# PFC_CurrentSensor_v3.net
KiCad netlist of a schematic drawn in Altium Designer
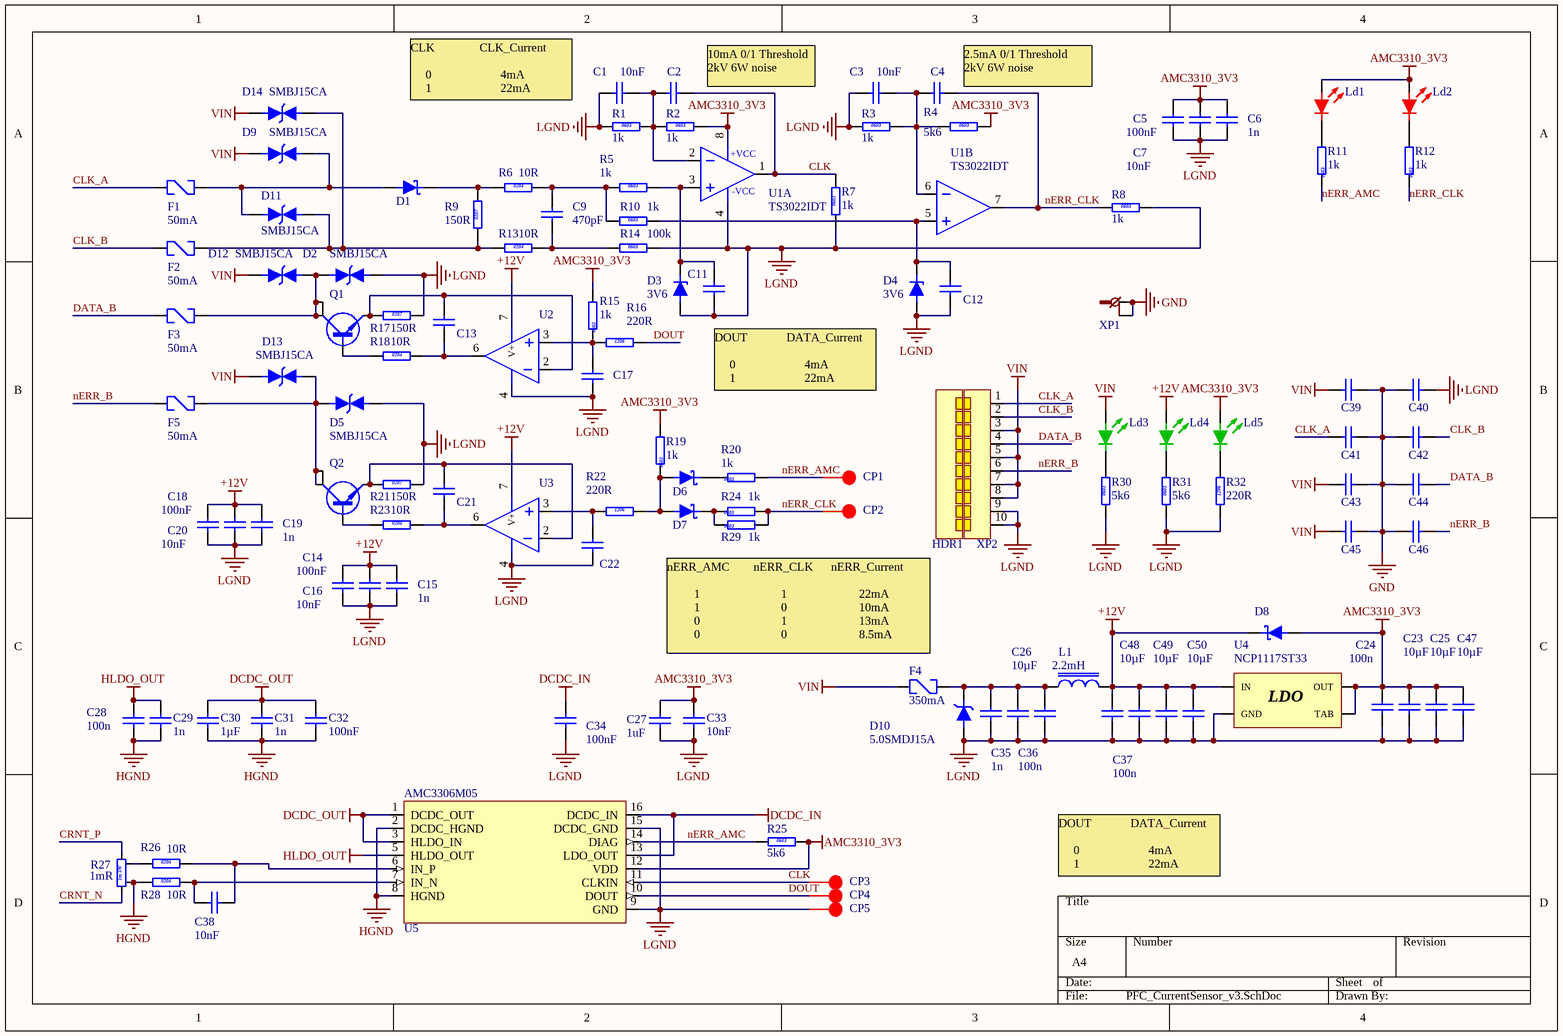
[diagram p0: PFC_CurrentSensor_v3.SchDoc]

(export (version "E")
  (design (tool "Eeschema 10.0.6"))
  (components
    (comp (ref "C1")
      (value "10nF")
      (footprint "CAP1206")
      (description "CAPACITOR UNPOLARIZED")
      (libsource (lib "components") (part "C103/50V/1206"))
    )
    (comp (ref "C2")
      (value "100p/100V/0603")
      (footprint "CAP0603")
      (description "CAPACITOR UNPOLARIZED")
      (libsource (lib "components") (part "C101/100V/0603"))
    )
    (comp (ref "C3")
      (value "10nF")
      (footprint "CAP1206")
      (description "CAPACITOR UNPOLARIZED")
      (libsource (lib "components") (part "C103/50V/1206"))
    )
    (comp (ref "C4")
      (value "100p/100V/0603")
      (footprint "CAP0603")
      (description "CAPACITOR UNPOLARIZED")
      (libsource (lib "components") (part "C101/100V/0603"))
    )
    (comp (ref "C5")
      (value "100nF")
      (footprint "CAP1206")
      (description "CAPACITOR UNPOLARIZED")
      (libsource (lib "components") (part "C104/50V/NP0/1206"))
    )
    (comp (ref "C6")
      (value "1n")
      (footprint "CAP0603")
      (description "CAPACITOR UNPOLARIZED")
      (libsource (lib "components") (part "C102/25V/0603"))
    )
    (comp (ref "C7")
      (value "10nF")
      (footprint "CAP1206")
      (description "CAPACITOR UNPOLARIZED")
      (libsource (lib "components") (part "C103/50V/1206"))
    )
    (comp (ref "C9")
      (value "470pF")
      (footprint "CAP1206")
      (description "CAPACITOR UNPOLARIZED")
      (libsource (lib "components") (part "C471/100V/1206/C0G"))
    )
    (comp (ref "C11")
      (value "100p/100V/0603")
      (footprint "CAP0603")
      (description "CAPACITOR UNPOLARIZED")
      (libsource (lib "components") (part "C101/100V/0603"))
    )
    (comp (ref "C12")
      (value "100p/100V/0603")
      (footprint "CAP0603")
      (description "CAPACITOR UNPOLARIZED")
      (libsource (lib "components") (part "C101/100V/0603"))
    )
    (comp (ref "C13")
      (value "100p/100V/0603")
      (footprint "CAP0603")
      (description "CAPACITOR UNPOLARIZED")
      (libsource (lib "components") (part "C101/100V/0603"))
    )
    (comp (ref "C14")
      (value "100nF")
      (footprint "CAP1206")
      (description "CAPACITOR UNPOLARIZED")
      (libsource (lib "components") (part "C104/50V/NP0/1206"))
    )
    (comp (ref "C15")
      (value "1n")
      (footprint "CAP0603")
      (description "CAPACITOR UNPOLARIZED")
      (libsource (lib "components") (part "C102/25V/0603"))
    )
    (comp (ref "C16")
      (value "10nF")
      (footprint "CAP1206")
      (description "CAPACITOR UNPOLARIZED")
      (libsource (lib "components") (part "C103/50V/1206"))
    )
    (comp (ref "C17")
      (value "100p/100V/0603")
      (footprint "CAP0603")
      (description "CAPACITOR UNPOLARIZED")
      (libsource (lib "components") (part "C101/100V/0603"))
    )
    (comp (ref "C18")
      (value "100nF")
      (footprint "CAP1206")
      (description "CAPACITOR UNPOLARIZED")
      (libsource (lib "components") (part "C104/50V/NP0/1206"))
    )
    (comp (ref "C19")
      (value "1n")
      (footprint "CAP0603")
      (description "CAPACITOR UNPOLARIZED")
      (libsource (lib "components") (part "C102/25V/0603"))
    )
    (comp (ref "C20")
      (value "10nF")
      (footprint "CAP1206")
      (description "CAPACITOR UNPOLARIZED")
      (libsource (lib "components") (part "C103/50V/1206"))
    )
    (comp (ref "C21")
      (value "100p/100V/0603")
      (footprint "CAP0603")
      (description "CAPACITOR UNPOLARIZED")
      (libsource (lib "components") (part "C101/100V/0603"))
    )
    (comp (ref "C22")
      (value "100p/100V/0603")
      (footprint "CAP0603")
      (description "CAPACITOR UNPOLARIZED")
      (libsource (lib "components") (part "C101/100V/0603"))
    )
    (comp (ref "C23")
      (value "10µF")
      (footprint "CAP1210")
      (description "CAPACITOR UNPOLARIZED")
      (libsource (lib "components") (part "C106/50V/1210"))
    )
    (comp (ref "C24")
      (value "100n")
      (footprint "CAP1812")
      (description "CAPACITOR UNPOLARIZED")
      (libsource (lib "components") (part "C104/1kV/1812"))
    )
    (comp (ref "C25")
      (value "10µF")
      (footprint "CAP1210")
      (description "CAPACITOR UNPOLARIZED")
      (libsource (lib "components") (part "C106/50V/1210"))
    )
    (comp (ref "C26")
      (value "10µF")
      (footprint "CAP1210")
      (description "CAPACITOR UNPOLARIZED")
      (libsource (lib "components") (part "C106/50V/1210"))
    )
    (comp (ref "C27")
      (value "1uF")
      (footprint "CAP1206")
      (description "CAPACITOR UNPOLARIZED")
      (libsource (lib "components") (part "C105/100V/1206"))
    )
    (comp (ref "C28")
      (value "100n")
      (footprint "CAP1812")
      (description "CAPACITOR UNPOLARIZED")
      (libsource (lib "components") (part "C104/1kV/1812"))
    )
    (comp (ref "C29")
      (value "1n")
      (footprint "CAP1812")
      (description "CAPACITOR UNPOLARIZED")
      (libsource (lib "components") (part "C102/1000V/1812/X7R"))
    )
    (comp (ref "C30")
      (value "1µF")
      (footprint "CAP0603")
      (description "CAPACITOR UNPOLARIZED")
      (libsource (lib "components") (part "C105/50V/0603"))
    )
    (comp (ref "C31")
      (value "1n")
      (footprint "CAP0603")
      (description "CAPACITOR UNPOLARIZED")
      (libsource (lib "components") (part "C102/25V/0603"))
    )
    (comp (ref "C32")
      (value "100nF")
      (footprint "CAP0603")
      (description "CAPACITOR UNPOLARIZED")
      (libsource (lib "components") (part "C104/50V/0603"))
    )
    (comp (ref "C33")
      (value "10nF")
      (footprint "CAP1206")
      (description "CAPACITOR UNPOLARIZED")
      (libsource (lib "components") (part "C103/50V/1206"))
    )
    (comp (ref "C34")
      (value "100nF")
      (footprint "CAP0603")
      (description "CAPACITOR UNPOLARIZED")
      (libsource (lib "components") (part "C104/50V/0603"))
    )
    (comp (ref "C35")
      (value "1n")
      (footprint "CAP1812")
      (description "CAPACITOR UNPOLARIZED")
      (libsource (lib "components") (part "C102/1000V/1812/X7R"))
    )
    (comp (ref "C36")
      (value "100n")
      (footprint "CAP1812")
      (description "CAPACITOR UNPOLARIZED")
      (libsource (lib "components") (part "C104/1kV/1812"))
    )
    (comp (ref "C37")
      (value "100n")
      (footprint "CAP1812")
      (description "CAPACITOR UNPOLARIZED")
      (libsource (lib "components") (part "C104/1kV/1812"))
    )
    (comp (ref "C38")
      (value "10nF")
      (footprint "CAP1206")
      (description "CAPACITOR UNPOLARIZED")
      (libsource (lib "components") (part "C103/50V/1206"))
    )
    (comp (ref "C39")
      (value "470p/1kV/1812/C0G")
      (footprint "CAP1812")
      (description "CAPACITOR UNPOLARIZED")
      (libsource (lib "components") (part "C471/1000V/1812/C0G"))
    )
    (comp (ref "C40")
      (value "470p/1kV/1812/C0G")
      (footprint "CAP1812")
      (description "CAPACITOR UNPOLARIZED")
      (libsource (lib "components") (part "C471/1000V/1812/C0G"))
    )
    (comp (ref "C41")
      (value "470p/1kV/1812/C0G")
      (footprint "CAP1812")
      (description "CAPACITOR UNPOLARIZED")
      (libsource (lib "components") (part "C471/1000V/1812/C0G"))
    )
    (comp (ref "C42")
      (value "470p/1kV/1812/C0G")
      (footprint "CAP1812")
      (description "CAPACITOR UNPOLARIZED")
      (libsource (lib "components") (part "C471/1000V/1812/C0G"))
    )
    (comp (ref "C43")
      (value "470p/1kV/1812/C0G")
      (footprint "CAP1812")
      (description "CAPACITOR UNPOLARIZED")
      (libsource (lib "components") (part "C471/1000V/1812/C0G"))
    )
    (comp (ref "C44")
      (value "470p/1kV/1812/C0G")
      (footprint "CAP1812")
      (description "CAPACITOR UNPOLARIZED")
      (libsource (lib "components") (part "C471/1000V/1812/C0G"))
    )
    (comp (ref "C45")
      (value "470p/1kV/1812/C0G")
      (footprint "CAP1812")
      (description "CAPACITOR UNPOLARIZED")
      (libsource (lib "components") (part "C471/1000V/1812/C0G"))
    )
    (comp (ref "C46")
      (value "470p/1kV/1812/C0G")
      (footprint "CAP1812")
      (description "CAPACITOR UNPOLARIZED")
      (libsource (lib "components") (part "C471/1000V/1812/C0G"))
    )
    (comp (ref "C47")
      (value "10µF")
      (footprint "CAP1210")
      (description "CAPACITOR UNPOLARIZED")
      (libsource (lib "components") (part "C106/50V/1210"))
    )
    (comp (ref "C48")
      (value "10µF")
      (footprint "CAP1210")
      (description "CAPACITOR UNPOLARIZED")
      (libsource (lib "components") (part "C106/50V/1210"))
    )
    (comp (ref "C49")
      (value "10µF")
      (footprint "CAP1210")
      (description "CAPACITOR UNPOLARIZED")
      (libsource (lib "components") (part "C106/50V/1210"))
    )
    (comp (ref "C50")
      (value "10µF")
      (footprint "CAP1210")
      (description "CAPACITOR UNPOLARIZED")
      (libsource (lib "components") (part "C106/50V/1210"))
    )
    (comp (ref "CP1")
      (value "CONTROL PAD")
      (footprint "CONTROL PAD")
      (libsource (lib "components") (part "CONTROL PAD"))
    )
    (comp (ref "CP2")
      (value "CONTROL PAD")
      (footprint "CONTROL PAD")
      (libsource (lib "components") (part "CONTROL PAD"))
    )
    (comp (ref "CP3")
      (value "CONTROL PAD")
      (footprint "CONTROL PAD")
      (libsource (lib "components") (part "CONTROL PAD"))
    )
    (comp (ref "CP4")
      (value "CONTROL PAD")
      (footprint "CONTROL PAD")
      (libsource (lib "components") (part "CONTROL PAD"))
    )
    (comp (ref "CP5")
      (value "CONTROL PAD")
      (footprint "CONTROL PAD")
      (libsource (lib "components") (part "CONTROL PAD"))
    )
    (comp (ref "D1")
      (value "B5819W/SOD123")
      (footprint "SOD123")
      (description "SCHOTTKY BARRIER DIODE/1A/40V/SOD123")
      (libsource (lib "components") (part "D/Schottky/B5819W/1A/40V/SOD123"))
    )
    (comp (ref "D2")
      (value "SMBJ15CA")
      (footprint "SMB")
      (description "TVS Diode")
      (libsource (lib "components") (part "SUP/SMBJ15CA/SMB"))
    )
    (comp (ref "D3")
      (value "3V6")
      (footprint "SMA")
      (description "Zener Diode")
      (libsource (lib "components") (part "D/ZENER/3.6V/BZG05C3V6/SMA"))
    )
    (comp (ref "D4")
      (value "3V6")
      (footprint "SMA")
      (description "Zener Diode")
      (libsource (lib "components") (part "D/ZENER/3.6V/BZG05C3V6/SMA"))
    )
    (comp (ref "D5")
      (value "SMBJ15CA")
      (footprint "SMB")
      (description "TVS Diode")
      (libsource (lib "components") (part "SUP/SMBJ15CA/SMB"))
    )
    (comp (ref "D6")
      (value "B5819W/SOD123")
      (footprint "SOD123")
      (description "SCHOTTKY BARRIER DIODE/1A/40V/SOD123")
      (libsource (lib "components") (part "D/Schottky/B5819W/1A/40V/SOD123"))
    )
    (comp (ref "D7")
      (value "B5819W/SOD123")
      (footprint "SOD123")
      (description "SCHOTTKY BARRIER DIODE/1A/40V/SOD123")
      (libsource (lib "components") (part "D/Schottky/B5819W/1A/40V/SOD123"))
    )
    (comp (ref "D8")
      (value "B5819W/SOD123")
      (footprint "SOD123")
      (description "SCHOTTKY BARRIER DIODE/1A/40V/SOD123")
      (libsource (lib "components") (part "D/Schottky/B5819W/1A/40V/SOD123"))
    )
    (comp (ref "D9")
      (value "SMBJ15CA")
      (footprint "SMB")
      (description "TVS Diode")
      (libsource (lib "components") (part "SUP/SMBJ15CA/SMB"))
    )
    (comp (ref "D10")
      (value "5.0SMDJ15A")
      (footprint "SMC")
      (description "TVS Diode")
      (libsource (lib "components") (part "SUP/5.0SMDJ15A/SMC"))
    )
    (comp (ref "D11")
      (value "SMBJ15CA")
      (footprint "SMB")
      (description "TVS Diode")
      (libsource (lib "components") (part "SUP/SMBJ15CA/SMB"))
    )
    (comp (ref "D12")
      (value "SMBJ15CA")
      (footprint "SMB")
      (description "TVS Diode")
      (libsource (lib "components") (part "SUP/SMBJ15CA/SMB"))
    )
    (comp (ref "D13")
      (value "SMBJ15CA")
      (footprint "SMB")
      (description "TVS Diode")
      (libsource (lib "components") (part "SUP/SMBJ15CA/SMB"))
    )
    (comp (ref "D14")
      (value "SMBJ15CA")
      (footprint "SMB")
      (description "TVS Diode")
      (libsource (lib "components") (part "SUP/SMBJ15CA/SMB"))
    )
    (comp (ref "F1")
      (value "50mA")
      (footprint "FUSE1206")
      (description "Resettable Fuses - PPTC PTC 60V POLYFUSE SURF MOUNT 1206 0.05A")
      (libsource (lib "components") (part "FUSE_RESETTABLE/50mA/1206"))
    )
    (comp (ref "F2")
      (value "50mA")
      (footprint "FUSE1206")
      (description "Resettable Fuses - PPTC PTC 60V POLYFUSE SURF MOUNT 1206 0.05A")
      (libsource (lib "components") (part "FUSE_RESETTABLE/50mA/1206"))
    )
    (comp (ref "F3")
      (value "50mA")
      (footprint "FUSE1206")
      (description "Resettable Fuses - PPTC PTC 60V POLYFUSE SURF MOUNT 1206 0.05A")
      (libsource (lib "components") (part "FUSE_RESETTABLE/50mA/1206"))
    )
    (comp (ref "F4")
      (value "350mA")
      (footprint "FUSE1206")
      (description "Resettable Fuses - PPTC .35A RESETTABLE SMD FUSE")
      (libsource (lib "components") (part "FUSE_RESETTABLE/350mA/1206"))
    )
    (comp (ref "F5")
      (value "50mA")
      (footprint "FUSE1206")
      (description "Resettable Fuses - PPTC PTC 60V POLYFUSE SURF MOUNT 1206 0.05A")
      (libsource (lib "components") (part "FUSE_RESETTABLE/50mA/1206"))
    )
    (comp (ref "HDR1")
      (value "2*5")
      (footprint "CON/MOLEX/2*5/2.00/FEMALE")
      (description "Headers & Wire Housings 2.00 mm")
      (libsource (lib "components") (part "CON/MOLEX/2*5/2.00/FEMALE"))
    )
    (comp (ref "L1")
      (value "2.2mH")
      (footprint "IND12.5X12.5MM")
      (description "INDUCTOR SMD")
      (libsource (lib "components") (part "L222/400mA/12.5*12.5"))
    )
    (comp (ref "Ld1")
      (value "R/0603")
      (footprint "LED0603")
      (description "LIGHT EMITTING DIODE")
      (libsource (lib "components") (part "LED/R/0603"))
    )
    (comp (ref "Ld2")
      (value "R/0603")
      (footprint "LED0603")
      (description "LIGHT EMITTING DIODE")
      (libsource (lib "components") (part "LED/R/0603"))
    )
    (comp (ref "Ld3")
      (value "G/0603")
      (footprint "LED0603")
      (description "LIGHT EMITTING DIODE")
      (libsource (lib "components") (part "LED/G/0603"))
    )
    (comp (ref "Ld4")
      (value "G/0603")
      (footprint "LED0603")
      (description "LIGHT EMITTING DIODE")
      (libsource (lib "components") (part "LED/G/0603"))
    )
    (comp (ref "Ld5")
      (value "G/0603")
      (footprint "LED0603")
      (description "LIGHT EMITTING DIODE")
      (libsource (lib "components") (part "LED/G/0603"))
    )
    (comp (ref "Q1")
      (value "BCP56/SOT223L")
      (footprint "SOT223L")
      (description "NPN SMD")
      (libsource (lib "components") (part "NPN_BCP56/SOT223L"))
    )
    (comp (ref "Q2")
      (value "BCP56/SOT223L")
      (footprint "SOT223L")
      (description "NPN SMD")
      (libsource (lib "components") (part "NPN_BCP56/SOT223L"))
    )
    (comp (ref "R1")
      (value "1k")
      (footprint "RES0603")
      (description "RESISTOR SMD")
      (libsource (lib "components") (part "R102/0603"))
    )
    (comp (ref "R2")
      (value "1k")
      (footprint "RES0603")
      (description "RESISTOR SMD")
      (libsource (lib "components") (part "R102/0603"))
    )
    (comp (ref "R3")
      (value "1k")
      (footprint "RES0603")
      (description "RESISTOR SMD")
      (libsource (lib "components") (part "R102/0603"))
    )
    (comp (ref "R4")
      (value "5k6")
      (footprint "RES0603")
      (description "RESISTOR SMD")
      (libsource (lib "components") (part "R562/0603"))
    )
    (comp (ref "R5")
      (value "1k")
      (footprint "RES0603")
      (description "RESISTOR SMD")
      (libsource (lib "components") (part "R102/0603"))
    )
    (comp (ref "R6")
      (value "10R")
      (footprint "MELF-0204")
      (description "RESISTOR SMD")
      (libsource (lib "components") (part "R100/0.5%/0204"))
    )
    (comp (ref "R7")
      (value "1k")
      (footprint "RES0603")
      (description "RESISTOR SMD")
      (libsource (lib "components") (part "R102/0603"))
    )
    (comp (ref "R8")
      (value "1k")
      (footprint "RES0603")
      (description "RESISTOR SMD")
      (libsource (lib "components") (part "R102/0603"))
    )
    (comp (ref "R9")
      (value "150R")
      (footprint "MELF-0207")
      (description "RESISTOR SMD MELF")
      (libsource (lib "components") (part "R151/0207"))
    )
    (comp (ref "R10")
      (value "1k")
      (footprint "RES0603")
      (description "RESISTOR SMD")
      (libsource (lib "components") (part "R102/0603"))
    )
    (comp (ref "R11")
      (value "1k")
      (footprint "RES0603")
      (description "RESISTOR SMD")
      (libsource (lib "components") (part "R102/0603"))
    )
    (comp (ref "R12")
      (value "1k")
      (footprint "RES0603")
      (description "RESISTOR SMD")
      (libsource (lib "components") (part "R102/0603"))
    )
    (comp (ref "R13")
      (value "10R")
      (footprint "MELF-0204")
      (description "RESISTOR SMD")
      (libsource (lib "components") (part "R100/0.5%/0204"))
    )
    (comp (ref "R14")
      (value "100k")
      (footprint "RES0603")
      (description "RESISTOR SMD")
      (libsource (lib "components") (part "R104/0603"))
    )
    (comp (ref "R15")
      (value "1k")
      (footprint "RES0603")
      (description "RESISTOR SMD")
      (libsource (lib "components") (part "R102/0603"))
    )
    (comp (ref "R16")
      (value "220R")
      (footprint "RES1206")
      (description "RESISTOR SMD")
      (libsource (lib "components") (part "R221/1206"))
    )
    (comp (ref "R17")
      (value "150R")
      (footprint "MELF-0207")
      (description "RESISTOR SMD MELF")
      (libsource (lib "components") (part "R151/0207"))
    )
    (comp (ref "R18")
      (value "10R")
      (footprint "MELF-0204")
      (description "RESISTOR SMD")
      (libsource (lib "components") (part "R100/0.5%/0204"))
    )
    (comp (ref "R19")
      (value "1k")
      (footprint "RES0603")
      (description "RESISTOR SMD")
      (libsource (lib "components") (part "R102/0603"))
    )
    (comp (ref "R20")
      (value "1k")
      (footprint "RES0603")
      (description "RESISTOR SMD")
      (libsource (lib "components") (part "R102/0603"))
    )
    (comp (ref "R21")
      (value "150R")
      (footprint "MELF-0207")
      (description "RESISTOR SMD MELF")
      (libsource (lib "components") (part "R151/0207"))
    )
    (comp (ref "R22")
      (value "220R")
      (footprint "RES1206")
      (description "RESISTOR SMD")
      (libsource (lib "components") (part "R221/1206"))
    )
    (comp (ref "R23")
      (value "10R")
      (footprint "MELF-0204")
      (description "RESISTOR SMD")
      (libsource (lib "components") (part "R100/0.5%/0204"))
    )
    (comp (ref "R24")
      (value "1k")
      (footprint "RES0603")
      (description "RESISTOR SMD")
      (libsource (lib "components") (part "R102/0603"))
    )
    (comp (ref "R25")
      (value "5k6")
      (footprint "RES0603")
      (description "RESISTOR SMD")
      (libsource (lib "components") (part "R562/0603"))
    )
    (comp (ref "R26")
      (value "10R")
      (footprint "MELF-0204")
      (description "RESISTOR SMD")
      (libsource (lib "components") (part "R100/0.5%/0204"))
    )
    (comp (ref "R27")
      (value "1mR")
      (footprint "RES-5W-4terminals_CurrensSense")
      (description "Current Sense Resistors - Through Hole 5W 0.001 Ohms 0.5%")
      (libsource (lib "components") (part "R1m/5W/TH/4 Terminal"))
    )
    (comp (ref "R28")
      (value "10R")
      (footprint "MELF-0204")
      (description "RESISTOR SMD")
      (libsource (lib "components") (part "R100/0.5%/0204"))
    )
    (comp (ref "R29")
      (value "1k")
      (footprint "RES0603")
      (description "RESISTOR SMD")
      (libsource (lib "components") (part "R102/0603"))
    )
    (comp (ref "R30")
      (value "5k6")
      (footprint "RES0603")
      (description "RESISTOR SMD")
      (libsource (lib "components") (part "R562/0603"))
    )
    (comp (ref "R31")
      (value "5k6")
      (footprint "RES0603")
      (description "RESISTOR SMD")
      (libsource (lib "components") (part "R562/0603"))
    )
    (comp (ref "R32")
      (value "220R")
      (footprint "RES1206")
      (description "RESISTOR SMD")
      (libsource (lib "components") (part "R221/1206"))
    )
    (comp (ref "TRML1")
      (value "CON/MOLEX/2*5/2.00/TERMILAL")
      (footprint "CON/MOLEX/2*5/2.00/TERMILAL")
      (description "Headers & Wire Housings 2.00 mm")
      (libsource (lib "components") (part "CON/MOLEX/2*5/2.00/TERMILAL"))
    )
    (comp (ref "TRML2")
      (value "CON/MOLEX/2*5/2.00/TERMILAL")
      (footprint "CON/MOLEX/2*5/2.00/TERMILAL")
      (description "Headers & Wire Housings 2.00 mm")
      (libsource (lib "components") (part "CON/MOLEX/2*5/2.00/TERMILAL"))
    )
    (comp (ref "TRML3")
      (value "CON/MOLEX/2*5/2.00/TERMILAL")
      (footprint "CON/MOLEX/2*5/2.00/TERMILAL")
      (description "Headers & Wire Housings 2.00 mm")
      (libsource (lib "components") (part "CON/MOLEX/2*5/2.00/TERMILAL"))
    )
    (comp (ref "TRML4")
      (value "CON/MOLEX/2*5/2.00/TERMILAL")
      (footprint "CON/MOLEX/2*5/2.00/TERMILAL")
      (description "Headers & Wire Housings 2.00 mm")
      (libsource (lib "components") (part "CON/MOLEX/2*5/2.00/TERMILAL"))
    )
    (comp (ref "TRML5")
      (value "CON/MOLEX/2*5/2.00/TERMILAL")
      (footprint "CON/MOLEX/2*5/2.00/TERMILAL")
      (description "Headers & Wire Housings 2.00 mm")
      (libsource (lib "components") (part "CON/MOLEX/2*5/2.00/TERMILAL"))
    )
    (comp (ref "TRML6")
      (value "CON/MOLEX/2*5/2.00/TERMILAL")
      (footprint "CON/MOLEX/2*5/2.00/TERMILAL")
      (description "Headers & Wire Housings 2.00 mm")
      (libsource (lib "components") (part "CON/MOLEX/2*5/2.00/TERMILAL"))
    )
    (comp (ref "TRML7")
      (value "CON/MOLEX/2*5/2.00/TERMILAL")
      (footprint "CON/MOLEX/2*5/2.00/TERMILAL")
      (description "Headers & Wire Housings 2.00 mm")
      (libsource (lib "components") (part "CON/MOLEX/2*5/2.00/TERMILAL"))
    )
    (comp (ref "TRML8")
      (value "CON/MOLEX/2*5/2.00/TERMILAL")
      (footprint "CON/MOLEX/2*5/2.00/TERMILAL")
      (description "Headers & Wire Housings 2.00 mm")
      (libsource (lib "components") (part "CON/MOLEX/2*5/2.00/TERMILAL"))
    )
    (comp (ref "TRML9")
      (value "CON/MOLEX/2*5/2.00/TERMILAL")
      (footprint "CON/MOLEX/2*5/2.00/TERMILAL")
      (description "Headers & Wire Housings 2.00 mm")
      (libsource (lib "components") (part "CON/MOLEX/2*5/2.00/TERMILAL"))
    )
    (comp (ref "TRML10")
      (value "CON/MOLEX/2*5/2.00/TERMILAL")
      (footprint "CON/MOLEX/2*5/2.00/TERMILAL")
      (description "Headers & Wire Housings 2.00 mm")
      (libsource (lib "components") (part "CON/MOLEX/2*5/2.00/TERMILAL"))
    )
    (comp (ref "U1")
      (value "TS3022IDT")
      (footprint "SO8_N")
      (description "Rail-to-rail 1.8 V high-speed dual comparator")
      (libsource (lib "components") (part "Comp/TS3022/5V/38ns/SOIC-8"))
    )
    (comp (ref "U2")
      (value "TLV197QDGKRQ1")
      (footprint "MS-8")
      (libsource (lib "components") (part "OpAmp/TLV197QDGKRQ1/40V/10mA/20V/us/10MHz/VSSOP-8"))
    )
    (comp (ref "U3")
      (value "TLV197QDGKRQ1")
      (footprint "MS-8")
      (libsource (lib "components") (part "OpAmp/TLV197QDGKRQ1/40V/10mA/20V/us/10MHz/VSSOP-8"))
    )
    (comp (ref "U4")
      (value "NCP1117ST33")
      (footprint "SOT223L")
      (description "LDO Voltage Regulators 3.3V 1A Positive")
      (libsource (lib "components") (part "LDO/NCP1117/3.3V/20V/1A/SOT223"))
    )
    (comp (ref "U5")
      (value "AMC3306M05")
      (footprint "SOIC-16W")
      (libsource (lib "components") (part "CurrentSensor/AMC3306M05DWE/SigmaDelta_ADC/50mV/SOIC16W"))
    )
    (comp (ref "XP1")
      (value "CON/1*1/5mm/M/Faston")
      (footprint "LS1560")
      (description "Terminals GDS-FLACHSTECK 6.3")
      (libsource (lib "components") (part "CON/1*1/5mm/M/Faston"))
    )
    (comp (ref "XP2")
      (value "2*5")
      (footprint "CON/MOLEX/2*5/2.00/SMT_MALE")
      (description "Headers & Wire Housings 2.00 mm")
      (libsource (lib "components") (part "CON/MOLEX/2*5/2.00/SMT_MALE"))
    )
  )
  (nets
    (net (code "1") (name "+12V") (class "Default")
      (node (ref "C14") (pin "1") (pinfunction "1_1") (pintype "passive"))
      (node (ref "C15") (pin "1") (pinfunction "1_1") (pintype "passive"))
      (node (ref "C16") (pin "2") (pinfunction "2_2") (pintype "passive"))
      (node (ref "C18") (pin "1") (pinfunction "1_1") (pintype "passive"))
      (node (ref "C19") (pin "1") (pinfunction "1_1") (pintype "passive"))
      (node (ref "C20") (pin "2") (pinfunction "2_2") (pintype "passive"))
      (node (ref "C37") (pin "1") (pinfunction "1_1") (pintype "passive"))
      (node (ref "C48") (pin "1") (pinfunction "1_1") (pintype "passive"))
      (node (ref "C49") (pin "1") (pinfunction "1_1") (pintype "passive"))
      (node (ref "C50") (pin "1") (pinfunction "1_1") (pintype "passive"))
      (node (ref "D8") (pin "2") (pinfunction "C_2") (pintype "passive"))
      (node (ref "L1") (pin "2") (pinfunction "2_2") (pintype "passive"))
      (node (ref "Ld4") (pin "1") (pinfunction "1_1") (pintype "passive"))
      (node (ref "U2") (pin "7") (pinfunction "V+_7") (pintype "power_in"))
      (node (ref "U3") (pin "7") (pinfunction "V+_7") (pintype "power_in"))
      (node (ref "U4") (pin "3") (pinfunction "IN_3") (pintype "passive"))
    )
    (net (code "2") (name "/CLK") (class "Default")
      (node (ref "C2") (pin "2") (pinfunction "2_2") (pintype "passive"))
      (node (ref "CP3") (pin "1") (pinfunction "1_1") (pintype "passive"))
      (node (ref "R7") (pin "1") (pinfunction "1_1") (pintype "passive"))
      (node (ref "U1") (pin "1") (pinfunction "OUT1_1") (pintype "passive"))
      (node (ref "U5") (pin "11") (pinfunction "CLKIN_11") (pintype "input"))
    )
    (net (code "3") (name "/CLK_A") (class "Default")
      (node (ref "C41") (pin "1") (pinfunction "1_1") (pintype "passive"))
      (node (ref "F1") (pin "2") (pinfunction "2_2") (pintype "passive"))
      (node (ref "XP2") (pin "1") (pinfunction "1_1") (pintype "passive"))
    )
    (net (code "4") (name "/CLK_B") (class "Default")
      (node (ref "C42") (pin "2") (pinfunction "2_2") (pintype "passive"))
      (node (ref "F2") (pin "2") (pinfunction "2_2") (pintype "passive"))
      (node (ref "XP2") (pin "2") (pinfunction "2_2") (pintype "passive"))
    )
    (net (code "5") (name "/CRNT_N") (class "Default")
      (node (ref "R27") (pin "1") (pinfunction "C1_1") (pintype "passive"))
    )
    (net (code "6") (name "/CRNT_P") (class "Default")
      (node (ref "R27") (pin "4") (pinfunction "C2_4") (pintype "passive"))
    )
    (net (code "7") (name "/DATA_B") (class "Default")
      (node (ref "C44") (pin "2") (pinfunction "2_2") (pintype "passive"))
      (node (ref "F3") (pin "2") (pinfunction "2_2") (pintype "passive"))
      (node (ref "XP2") (pin "4") (pinfunction "4_4") (pintype "passive"))
    )
    (net (code "8") (name "/DOUT") (class "Default")
      (node (ref "CP4") (pin "1") (pinfunction "1_1") (pintype "passive"))
      (node (ref "R16") (pin "1") (pinfunction "1_1") (pintype "passive"))
      (node (ref "U5") (pin "10") (pinfunction "DOUT_10") (pintype "output"))
    )
    (net (code "9") (name "/nERR_AMC") (class "Default")
      (node (ref "CP1") (pin "1") (pinfunction "1_1") (pintype "passive"))
      (node (ref "R11") (pin "2") (pinfunction "2_2") (pintype "passive"))
      (node (ref "R20") (pin "1") (pinfunction "1_1") (pintype "passive"))
      (node (ref "R25") (pin "2") (pinfunction "2_2") (pintype "passive"))
      (node (ref "U5") (pin "14") (pinfunction "DIAG_14") (pintype "output"))
    )
    (net (code "10") (name "/nERR_B") (class "Default")
      (node (ref "C46") (pin "2") (pinfunction "2_2") (pintype "passive"))
      (node (ref "F5") (pin "2") (pinfunction "2_2") (pintype "passive"))
      (node (ref "XP2") (pin "6") (pinfunction "6_6") (pintype "passive"))
    )
    (net (code "11") (name "/nERR_CLK") (class "Default")
      (node (ref "C4") (pin "2") (pinfunction "2_2") (pintype "passive"))
      (node (ref "CP2") (pin "1") (pinfunction "1_1") (pintype "passive"))
      (node (ref "R12") (pin "2") (pinfunction "2_2") (pintype "passive"))
      (node (ref "R24") (pin "1") (pinfunction "1_1") (pintype "passive"))
      (node (ref "R29") (pin "1") (pinfunction "1_1") (pintype "passive"))
      (node (ref "R8") (pin "2") (pinfunction "2_2") (pintype "passive"))
      (node (ref "U1") (pin "7") (pinfunction "OUT2_7") (pintype "passive"))
    )
    (net (code "12") (name "AMC3310_3V3") (class "Default")
      (node (ref "C23") (pin "1") (pinfunction "1_1") (pintype "passive"))
      (node (ref "C24") (pin "1") (pinfunction "1_1") (pintype "passive"))
      (node (ref "C25") (pin "1") (pinfunction "1_1") (pintype "passive"))
      (node (ref "C27") (pin "1") (pinfunction "1_1") (pintype "passive"))
      (node (ref "C33") (pin "1") (pinfunction "1_1") (pintype "passive"))
      (node (ref "C47") (pin "1") (pinfunction "1_1") (pintype "passive"))
      (node (ref "C5") (pin "1") (pinfunction "1_1") (pintype "passive"))
      (node (ref "C6") (pin "1") (pinfunction "1_1") (pintype "passive"))
      (node (ref "C7") (pin "2") (pinfunction "2_2") (pintype "passive"))
      (node (ref "D8") (pin "1") (pinfunction "A_1") (pintype "passive"))
      (node (ref "Ld1") (pin "1") (pinfunction "1_1") (pintype "passive"))
      (node (ref "Ld2") (pin "1") (pinfunction "1_1") (pintype "passive"))
      (node (ref "Ld5") (pin "1") (pinfunction "1_1") (pintype "passive"))
      (node (ref "R15") (pin "1") (pinfunction "1_1") (pintype "passive"))
      (node (ref "R19") (pin "1") (pinfunction "1_1") (pintype "passive"))
      (node (ref "R2") (pin "1") (pinfunction "1_1") (pintype "passive"))
      (node (ref "R25") (pin "1") (pinfunction "1_1") (pintype "passive"))
      (node (ref "R4") (pin "1") (pinfunction "1_1") (pintype "passive"))
      (node (ref "U1") (pin "8") (pinfunction "V+_8") (pintype "power_in"))
      (node (ref "U4") (pin "2") (pinfunction "OUT_2") (pintype "passive"))
      (node (ref "U4") (pin "4") (pinfunction "TAB_4") (pintype "passive"))
      (node (ref "U5") (pin "12") (pinfunction "VDD_12") (pintype "passive"))
    )
    (net (code "13") (name "DCDC_IN") (class "Default")
      (node (ref "C34") (pin "2") (pinfunction "2_2") (pintype "passive"))
      (node (ref "U5") (pin "13") (pinfunction "LDO_OUT_13") (pintype "passive"))
      (node (ref "U5") (pin "16") (pinfunction "DCDC_IN_16") (pintype "power_in"))
    )
    (net (code "14") (name "DCDC_OUT") (class "Default")
      (node (ref "C30") (pin "1") (pinfunction "1_1") (pintype "passive"))
      (node (ref "C31") (pin "1") (pinfunction "1_1") (pintype "passive"))
      (node (ref "C32") (pin "2") (pinfunction "2_2") (pintype "passive"))
      (node (ref "U5") (pin "1") (pinfunction "DCDC_OUT_1") (pintype "power_in"))
      (node (ref "U5") (pin "3") (pinfunction "HLDO_IN_3") (pintype "power_in"))
    )
    (net (code "15") (name "GND") (class "Default")
      (node (ref "C39") (pin "2") (pinfunction "2_2") (pintype "passive"))
      (node (ref "C40") (pin "1") (pinfunction "1_1") (pintype "passive"))
      (node (ref "C41") (pin "2") (pinfunction "2_2") (pintype "passive"))
      (node (ref "C42") (pin "1") (pinfunction "1_1") (pintype "passive"))
      (node (ref "C43") (pin "2") (pinfunction "2_2") (pintype "passive"))
      (node (ref "C44") (pin "1") (pinfunction "1_1") (pintype "passive"))
      (node (ref "C45") (pin "2") (pinfunction "2_2") (pintype "passive"))
      (node (ref "C46") (pin "1") (pinfunction "1_1") (pintype "passive"))
      (node (ref "XP1") (pin "1") (pinfunction "P$1_1") (pintype "passive"))
      (node (ref "XP1") (pin "1A") (pinfunction "P$2_1A") (pintype "passive"))
    )
    (net (code "16") (name "HGND") (class "Default")
      (node (ref "C28") (pin "2") (pinfunction "2_2") (pintype "passive"))
      (node (ref "C29") (pin "2") (pinfunction "2_2") (pintype "passive"))
      (node (ref "C30") (pin "2") (pinfunction "2_2") (pintype "passive"))
      (node (ref "C31") (pin "2") (pinfunction "2_2") (pintype "passive"))
      (node (ref "C32") (pin "1") (pinfunction "1_1") (pintype "passive"))
      (node (ref "R27") (pin "2") (pinfunction "S1_2") (pintype "passive"))
      (node (ref "R28") (pin "2") (pinfunction "2_2") (pintype "passive"))
      (node (ref "U5") (pin "2") (pinfunction "DCDC_HGND_2") (pintype "power_in"))
      (node (ref "U5") (pin "8") (pinfunction "HGND_8") (pintype "power_in"))
    )
    (net (code "17") (name "HLDO_OUT") (class "Default")
      (node (ref "C28") (pin "1") (pinfunction "1_1") (pintype "passive"))
      (node (ref "C29") (pin "1") (pinfunction "1_1") (pintype "passive"))
      (node (ref "U5") (pin "5") (pinfunction "HLDO_OUT_5") (pintype "power_in"))
    )
    (net (code "18") (name "LGND") (class "Default")
      (node (ref "C1") (pin "2") (pinfunction "2_2") (pintype "passive"))
      (node (ref "C11") (pin "1") (pinfunction "1_1") (pintype "passive"))
      (node (ref "C12") (pin "1") (pinfunction "1_1") (pintype "passive"))
      (node (ref "C14") (pin "2") (pinfunction "2_2") (pintype "passive"))
      (node (ref "C15") (pin "2") (pinfunction "2_2") (pintype "passive"))
      (node (ref "C16") (pin "1") (pinfunction "1_1") (pintype "passive"))
      (node (ref "C17") (pin "2") (pinfunction "2_2") (pintype "passive"))
      (node (ref "C18") (pin "2") (pinfunction "2_2") (pintype "passive"))
      (node (ref "C19") (pin "2") (pinfunction "2_2") (pintype "passive"))
      (node (ref "C20") (pin "1") (pinfunction "1_1") (pintype "passive"))
      (node (ref "C22") (pin "2") (pinfunction "2_2") (pintype "passive"))
      (node (ref "C23") (pin "2") (pinfunction "2_2") (pintype "passive"))
      (node (ref "C24") (pin "2") (pinfunction "2_2") (pintype "passive"))
      (node (ref "C25") (pin "2") (pinfunction "2_2") (pintype "passive"))
      (node (ref "C26") (pin "2") (pinfunction "2_2") (pintype "passive"))
      (node (ref "C27") (pin "2") (pinfunction "2_2") (pintype "passive"))
      (node (ref "C3") (pin "2") (pinfunction "2_2") (pintype "passive"))
      (node (ref "C33") (pin "2") (pinfunction "2_2") (pintype "passive"))
      (node (ref "C34") (pin "1") (pinfunction "1_1") (pintype "passive"))
      (node (ref "C35") (pin "2") (pinfunction "2_2") (pintype "passive"))
      (node (ref "C36") (pin "2") (pinfunction "2_2") (pintype "passive"))
      (node (ref "C37") (pin "2") (pinfunction "2_2") (pintype "passive"))
      (node (ref "C40") (pin "2") (pinfunction "2_2") (pintype "passive"))
      (node (ref "C47") (pin "2") (pinfunction "2_2") (pintype "passive"))
      (node (ref "C48") (pin "2") (pinfunction "2_2") (pintype "passive"))
      (node (ref "C49") (pin "2") (pinfunction "2_2") (pintype "passive"))
      (node (ref "C5") (pin "2") (pinfunction "2_2") (pintype "passive"))
      (node (ref "C50") (pin "2") (pinfunction "2_2") (pintype "passive"))
      (node (ref "C6") (pin "2") (pinfunction "2_2") (pintype "passive"))
      (node (ref "C7") (pin "1") (pinfunction "1_1") (pintype "passive"))
      (node (ref "CP5") (pin "1") (pinfunction "1_1") (pintype "passive"))
      (node (ref "D10") (pin "1") (pinfunction "A_1") (pintype "passive"))
      (node (ref "D2") (pin "1") (pinfunction "A_1") (pintype "passive"))
      (node (ref "D3") (pin "1") (pinfunction "A_1") (pintype "passive"))
      (node (ref "D4") (pin "1") (pinfunction "A_1") (pintype "passive"))
      (node (ref "D5") (pin "1") (pinfunction "A_1") (pintype "passive"))
      (node (ref "R1") (pin "2") (pinfunction "2_2") (pintype "passive"))
      (node (ref "R14") (pin "1") (pinfunction "1_1") (pintype "passive"))
      (node (ref "R17") (pin "1") (pinfunction "1_1") (pintype "passive"))
      (node (ref "R21") (pin "1") (pinfunction "1_1") (pintype "passive"))
      (node (ref "R3") (pin "2") (pinfunction "2_2") (pintype "passive"))
      (node (ref "R30") (pin "2") (pinfunction "2_2") (pintype "passive"))
      (node (ref "R31") (pin "2") (pinfunction "2_2") (pintype "passive"))
      (node (ref "R32") (pin "2") (pinfunction "2_2") (pintype "passive"))
      (node (ref "R7") (pin "2") (pinfunction "2_2") (pintype "passive"))
      (node (ref "R8") (pin "1") (pinfunction "1_1") (pintype "passive"))
      (node (ref "U1") (pin "4") (pinfunction "V-_4") (pintype "power_in"))
      (node (ref "U2") (pin "4") (pinfunction "Vee_4") (pintype "power_in"))
      (node (ref "U3") (pin "4") (pinfunction "Vee_4") (pintype "power_in"))
      (node (ref "U4") (pin "1") (pinfunction "GND_1") (pintype "passive"))
      (node (ref "U5") (pin "15") (pinfunction "DCDC_GND_15") (pintype "passive"))
      (node (ref "U5") (pin "9") (pinfunction "GND_9") (pintype "power_in"))
      (node (ref "XP2") (pin "10") (pinfunction "10_10") (pintype "passive"))
      (node (ref "XP2") (pin "9") (pinfunction "9_9") (pintype "passive"))
    )
    (net (code "19") (name "Net-(C9-Pad1)") (class "Default")
      (node (ref "C9") (pin "1") (pinfunction "1_1") (pintype "passive"))
      (node (ref "R10") (pin "2") (pinfunction "2_2") (pintype "passive"))
      (node (ref "R5") (pin "2") (pinfunction "2_2") (pintype "passive"))
      (node (ref "R6") (pin "1") (pinfunction "1_1") (pintype "passive"))
    )
    (net (code "20") (name "Net-(C9-Pad2)") (class "Default")
      (node (ref "C9") (pin "2") (pinfunction "2_2") (pintype "passive"))
      (node (ref "R13") (pin "1") (pinfunction "1_1") (pintype "passive"))
      (node (ref "R14") (pin "2") (pinfunction "2_2") (pintype "passive"))
    )
    (net (code "21") (name "Net-(D1-A)") (class "Default")
      (node (ref "D1") (pin "1") (pinfunction "A_1") (pintype "passive"))
      (node (ref "D11") (pin "2") (pinfunction "C_2") (pintype "passive"))
      (node (ref "D9") (pin "1") (pinfunction "A_1") (pintype "passive"))
      (node (ref "F1") (pin "1") (pinfunction "1_1") (pintype "passive"))
    )
    (net (code "22") (name "Net-(D1-C)") (class "Default")
      (node (ref "D1") (pin "2") (pinfunction "C_2") (pintype "passive"))
      (node (ref "R6") (pin "2") (pinfunction "2_2") (pintype "passive"))
      (node (ref "R9") (pin "1") (pinfunction "1_1") (pintype "passive"))
    )
    (net (code "23") (name "Net-(D3-C)") (class "Default")
      (node (ref "C11") (pin "2") (pinfunction "2_2") (pintype "passive"))
      (node (ref "D3") (pin "2") (pinfunction "C_2") (pintype "passive"))
      (node (ref "R5") (pin "1") (pinfunction "1_1") (pintype "passive"))
      (node (ref "U1") (pin "3") (pinfunction "IN+1_3") (pintype "passive"))
    )
    (net (code "24") (name "Net-(D4-C)") (class "Default")
      (node (ref "C12") (pin "2") (pinfunction "2_2") (pintype "passive"))
      (node (ref "D4") (pin "2") (pinfunction "C_2") (pintype "passive"))
      (node (ref "R10") (pin "1") (pinfunction "1_1") (pintype "passive"))
      (node (ref "U1") (pin "5") (pinfunction "IN+2_5") (pintype "passive"))
    )
    (net (code "25") (name "Net-(D6-A)") (class "Default")
      (node (ref "D6") (pin "1") (pinfunction "A_1") (pintype "passive"))
      (node (ref "D7") (pin "1") (pinfunction "A_1") (pintype "passive"))
      (node (ref "R19") (pin "2") (pinfunction "2_2") (pintype "passive"))
      (node (ref "R22") (pin "1") (pinfunction "1_1") (pintype "passive"))
    )
    (net (code "26") (name "Net-(D6-C)") (class "Default")
      (node (ref "D6") (pin "2") (pinfunction "C_2") (pintype "passive"))
      (node (ref "R20") (pin "2") (pinfunction "2_2") (pintype "passive"))
    )
    (net (code "27") (name "Net-(D7-C)") (class "Default")
      (node (ref "D7") (pin "2") (pinfunction "C_2") (pintype "passive"))
      (node (ref "R24") (pin "2") (pinfunction "2_2") (pintype "passive"))
      (node (ref "R29") (pin "2") (pinfunction "2_2") (pintype "passive"))
    )
    (net (code "28") (name "Net-(D10-C)") (class "Default")
      (node (ref "C26") (pin "1") (pinfunction "1_1") (pintype "passive"))
      (node (ref "C35") (pin "1") (pinfunction "1_1") (pintype "passive"))
      (node (ref "C36") (pin "1") (pinfunction "1_1") (pintype "passive"))
      (node (ref "D10") (pin "2") (pinfunction "C_2") (pintype "passive"))
      (node (ref "F4") (pin "1") (pinfunction "1_1") (pintype "passive"))
      (node (ref "L1") (pin "1") (pinfunction "1_1") (pintype "passive"))
    )
    (net (code "29") (name "Net-(D11-A)") (class "Default")
      (node (ref "D11") (pin "1") (pinfunction "A_1") (pintype "passive"))
      (node (ref "D14") (pin "1") (pinfunction "A_1") (pintype "passive"))
      (node (ref "F2") (pin "1") (pinfunction "1_1") (pintype "passive"))
      (node (ref "R13") (pin "2") (pinfunction "2_2") (pintype "passive"))
      (node (ref "R9") (pin "2") (pinfunction "2_2") (pintype "passive"))
    )
    (net (code "30") (name "Net-(D12-C)") (class "Default")
      (node (ref "D12") (pin "2") (pinfunction "C_2") (pintype "passive"))
      (node (ref "D2") (pin "2") (pinfunction "C_2") (pintype "passive"))
      (node (ref "F3") (pin "1") (pinfunction "1_1") (pintype "passive"))
      (node (ref "Q1") (pin "2") (pinfunction "C_2") (pintype "open_collector"))
      (node (ref "Q1") (pin "4") (pinfunction "S_4") (pintype "open_collector"))
    )
    (net (code "31") (name "Net-(D13-C)") (class "Default")
      (node (ref "D13") (pin "2") (pinfunction "C_2") (pintype "passive"))
      (node (ref "D5") (pin "2") (pinfunction "C_2") (pintype "passive"))
      (node (ref "F5") (pin "1") (pinfunction "1_1") (pintype "passive"))
      (node (ref "Q2") (pin "2") (pinfunction "C_2") (pintype "open_collector"))
      (node (ref "Q2") (pin "4") (pinfunction "S_4") (pintype "open_collector"))
    )
    (net (code "32") (name "Net-(Ld1-Pad2)") (class "Default")
      (node (ref "Ld1") (pin "2") (pinfunction "2_2") (pintype "passive"))
      (node (ref "R11") (pin "1") (pinfunction "1_1") (pintype "passive"))
    )
    (net (code "33") (name "Net-(Ld2-Pad2)") (class "Default")
      (node (ref "Ld2") (pin "2") (pinfunction "2_2") (pintype "passive"))
      (node (ref "R12") (pin "1") (pinfunction "1_1") (pintype "passive"))
    )
    (net (code "34") (name "Net-(Ld3-Pad2)") (class "Default")
      (node (ref "Ld3") (pin "2") (pinfunction "2_2") (pintype "passive"))
      (node (ref "R30") (pin "1") (pinfunction "1_1") (pintype "passive"))
    )
    (net (code "35") (name "Net-(Ld4-Pad2)") (class "Default")
      (node (ref "Ld4") (pin "2") (pinfunction "2_2") (pintype "passive"))
      (node (ref "R31") (pin "1") (pinfunction "1_1") (pintype "passive"))
    )
    (net (code "36") (name "Net-(Ld5-Pad2)") (class "Default")
      (node (ref "Ld5") (pin "2") (pinfunction "2_2") (pintype "passive"))
      (node (ref "R32") (pin "1") (pinfunction "1_1") (pintype "passive"))
    )
    (net (code "37") (name "Net-(Q1-B)") (class "Default")
      (node (ref "Q1") (pin "1") (pinfunction "B_1") (pintype "passive"))
      (node (ref "R18") (pin "2") (pinfunction "2_2") (pintype "passive"))
    )
    (net (code "38") (name "Net-(Q1-E)") (class "Default")
      (node (ref "C13") (pin "2") (pinfunction "2_2") (pintype "passive"))
      (node (ref "Q1") (pin "3") (pinfunction "E_3") (pintype "open_emitter"))
      (node (ref "R17") (pin "2") (pinfunction "2_2") (pintype "passive"))
      (node (ref "U2") (pin "2") (pinfunction "IN-_2") (pintype "passive"))
    )
    (net (code "39") (name "Net-(Q2-B)") (class "Default")
      (node (ref "Q2") (pin "1") (pinfunction "B_1") (pintype "passive"))
      (node (ref "R23") (pin "2") (pinfunction "2_2") (pintype "passive"))
    )
    (net (code "40") (name "Net-(Q2-E)") (class "Default")
      (node (ref "C21") (pin "2") (pinfunction "2_2") (pintype "passive"))
      (node (ref "Q2") (pin "3") (pinfunction "E_3") (pintype "open_emitter"))
      (node (ref "R21") (pin "2") (pinfunction "2_2") (pintype "passive"))
      (node (ref "U3") (pin "2") (pinfunction "IN-_2") (pintype "passive"))
    )
    (net (code "41") (name "Net-(R27-S2)") (class "Default")
      (node (ref "R26") (pin "2") (pinfunction "2_2") (pintype "passive"))
      (node (ref "R27") (pin "3") (pinfunction "S2_3") (pintype "passive"))
    )
    (net (code "42") (name "Net-(U1A-IN-1)") (class "Default")
      (node (ref "C1") (pin "1") (pinfunction "1_1") (pintype "passive"))
      (node (ref "C2") (pin "1") (pinfunction "1_1") (pintype "passive"))
      (node (ref "R1") (pin "1") (pinfunction "1_1") (pintype "passive"))
      (node (ref "R2") (pin "2") (pinfunction "2_2") (pintype "passive"))
      (node (ref "U1") (pin "2") (pinfunction "IN-1_2") (pintype "passive"))
    )
    (net (code "43") (name "Net-(U1B-IN-2)") (class "Default")
      (node (ref "C3") (pin "1") (pinfunction "1_1") (pintype "passive"))
      (node (ref "C4") (pin "1") (pinfunction "1_1") (pintype "passive"))
      (node (ref "R3") (pin "1") (pinfunction "1_1") (pintype "passive"))
      (node (ref "R4") (pin "2") (pinfunction "2_2") (pintype "passive"))
      (node (ref "U1") (pin "6") (pinfunction "IN-2_6") (pintype "passive"))
    )
    (net (code "44") (name "Net-(U2-IN+)") (class "Default")
      (node (ref "C17") (pin "1") (pinfunction "1_1") (pintype "passive"))
      (node (ref "R15") (pin "2") (pinfunction "2_2") (pintype "passive"))
      (node (ref "R16") (pin "2") (pinfunction "2_2") (pintype "passive"))
      (node (ref "U2") (pin "3") (pinfunction "IN+_3") (pintype "passive"))
    )
    (net (code "45") (name "Net-(U2-OUT1)") (class "Default")
      (node (ref "C13") (pin "1") (pinfunction "1_1") (pintype "passive"))
      (node (ref "R18") (pin "1") (pinfunction "1_1") (pintype "passive"))
      (node (ref "U2") (pin "6") (pinfunction "OUT1_6") (pintype "passive"))
    )
    (net (code "46") (name "Net-(U3-IN+)") (class "Default")
      (node (ref "C22") (pin "1") (pinfunction "1_1") (pintype "passive"))
      (node (ref "R22") (pin "2") (pinfunction "2_2") (pintype "passive"))
      (node (ref "U3") (pin "3") (pinfunction "IN+_3") (pintype "passive"))
    )
    (net (code "47") (name "Net-(U3-OUT1)") (class "Default")
      (node (ref "C21") (pin "1") (pinfunction "1_1") (pintype "passive"))
      (node (ref "R23") (pin "1") (pinfunction "1_1") (pintype "passive"))
      (node (ref "U3") (pin "6") (pinfunction "OUT1_6") (pintype "passive"))
    )
    (net (code "48") (name "Net-(U5-IN_N)") (class "Default")
      (node (ref "C38") (pin "1") (pinfunction "1_1") (pintype "passive"))
      (node (ref "R28") (pin "1") (pinfunction "1_1") (pintype "passive"))
      (node (ref "U5") (pin "7") (pinfunction "IN_N_7") (pintype "input"))
    )
    (net (code "49") (name "Net-(U5-IN_P)") (class "Default")
      (node (ref "C38") (pin "2") (pinfunction "2_2") (pintype "passive"))
      (node (ref "R26") (pin "1") (pinfunction "1_1") (pintype "passive"))
      (node (ref "U5") (pin "6") (pinfunction "IN_P_6") (pintype "input"))
    )
    (net (code "50") (name "VIN") (class "Default")
      (node (ref "C39") (pin "1") (pinfunction "1_1") (pintype "passive"))
      (node (ref "C43") (pin "1") (pinfunction "1_1") (pintype "passive"))
      (node (ref "C45") (pin "1") (pinfunction "1_1") (pintype "passive"))
      (node (ref "D12") (pin "1") (pinfunction "A_1") (pintype "passive"))
      (node (ref "D13") (pin "1") (pinfunction "A_1") (pintype "passive"))
      (node (ref "D14") (pin "2") (pinfunction "C_2") (pintype "passive"))
      (node (ref "D9") (pin "2") (pinfunction "C_2") (pintype "passive"))
      (node (ref "F4") (pin "2") (pinfunction "2_2") (pintype "passive"))
      (node (ref "Ld3") (pin "1") (pinfunction "1_1") (pintype "passive"))
      (node (ref "XP2") (pin "3") (pinfunction "3_3") (pintype "passive"))
      (node (ref "XP2") (pin "5") (pinfunction "5_5") (pintype "passive"))
      (node (ref "XP2") (pin "7") (pinfunction "7_7") (pintype "passive"))
      (node (ref "XP2") (pin "8") (pinfunction "8_8") (pintype "passive"))
    )
  )
)
